# Capteur_Therm.net
KiCad netlist of a schematic drawn in Altium Designer
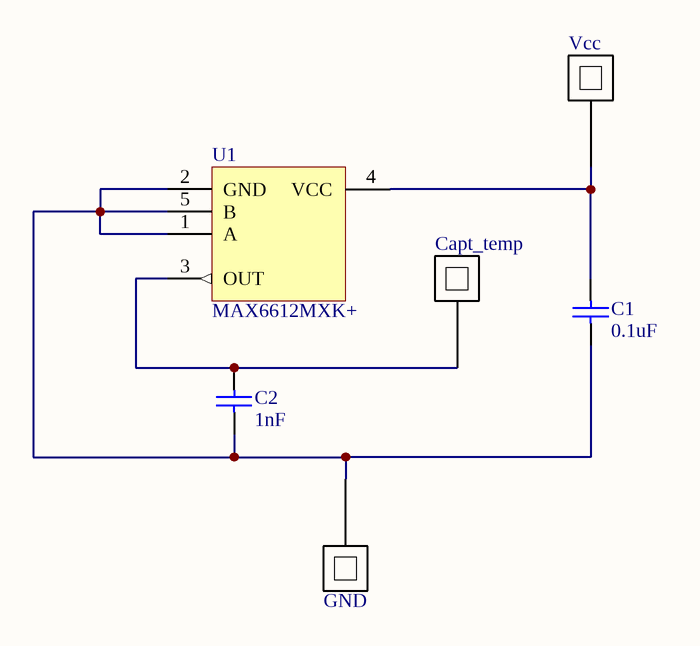
[diagram p0: Capteur_Therm.SchDoc]

(export (version "E")
  (design (tool "Eeschema 10.0.6"))
  (components
    (comp (ref "C1")
      (value "0.1uF")
      (footprint "C0805")
      (description "Cap 100nF")
      (fields (field (name "Comment") "Cap") (field (name "PUBLISHER") "Altium Limited"))
      (libsource (lib "Miscellaneous Devices") (part "Cap"))
    )
    (comp (ref "C2")
      (value "1nF")
      (footprint "C0805")
      (description "Cap 1nF")
      (fields (field (name "Comment") "Cap") (field (name "PUBLISHER") "Altium Limited"))
      (libsource (lib "Miscellaneous Devices") (part "Cap"))
    )
    (comp (ref "Capt_temp")
      (value "Capt_temp")
      (footprint "PIN1")
      (description "CONN HEADER VERT 1POS")
      (libsource (lib "2019_RegThermiqueMyRio") (part "Berg"))
    )
    (comp (ref "GND")
      (value "GND")
      (footprint "PIN1")
      (description "CONN HEADER VERT 1POS")
      (libsource (lib "") (part "Berg_1"))
    )
    (comp (ref "U1")
      (value "MAX6612MXK+")
      (footprint "MAXM-X5+1_M")
      (description "High-Slope, Low-Power, Analog Temperature Sensor, -55 to 150 degC, 5-Pin SOT23 (X5+1), Pb-Free")
      (fields (field (name "GENERIC PART NUMBER") "MAX6612"))
      (libsource (lib "Altium Content Vault") (part "MAX6612-X5"))
    )
    (comp (ref "Vcc")
      (value "3V3")
      (footprint "PIN1")
      (description "CONN HEADER VERT 1POS")
      (libsource (lib "2019_RegThermiqueMyRio") (part "Berg"))
    )
  )
  (nets
    (net (code "1") (name "Net-(U1-A)") (class "Default")
      (node (ref "C1") (pin "2") (pinfunction "2_2") (pintype "passive"))
      (node (ref "C2") (pin "2") (pinfunction "2_2") (pintype "passive"))
      (node (ref "GND") (pin "1") (pinfunction "1_1") (pintype "passive"))
      (node (ref "U1") (pin "1") (pinfunction "A_1") (pintype "power_in"))
      (node (ref "U1") (pin "2") (pinfunction "GND_2") (pintype "power_in"))
      (node (ref "U1") (pin "5") (pinfunction "B_5") (pintype "power_in"))
    )
    (net (code "2") (name "Net-(U1-OUT)") (class "Default")
      (node (ref "C2") (pin "1") (pinfunction "1_1") (pintype "passive"))
      (node (ref "Capt_temp") (pin "1") (pinfunction "1_1") (pintype "passive"))
      (node (ref "U1") (pin "3") (pinfunction "OUT_3") (pintype "output"))
    )
    (net (code "3") (name "Net-(U1-VCC)") (class "Default")
      (node (ref "C1") (pin "1") (pinfunction "1_1") (pintype "passive"))
      (node (ref "U1") (pin "4") (pinfunction "VCC_4") (pintype "passive"))
      (node (ref "Vcc") (pin "1") (pinfunction "1_1") (pintype "passive"))
    )
  )
)
